# LED_ARRAY.net
KiCad netlist of a schematic drawn in Altium Designer
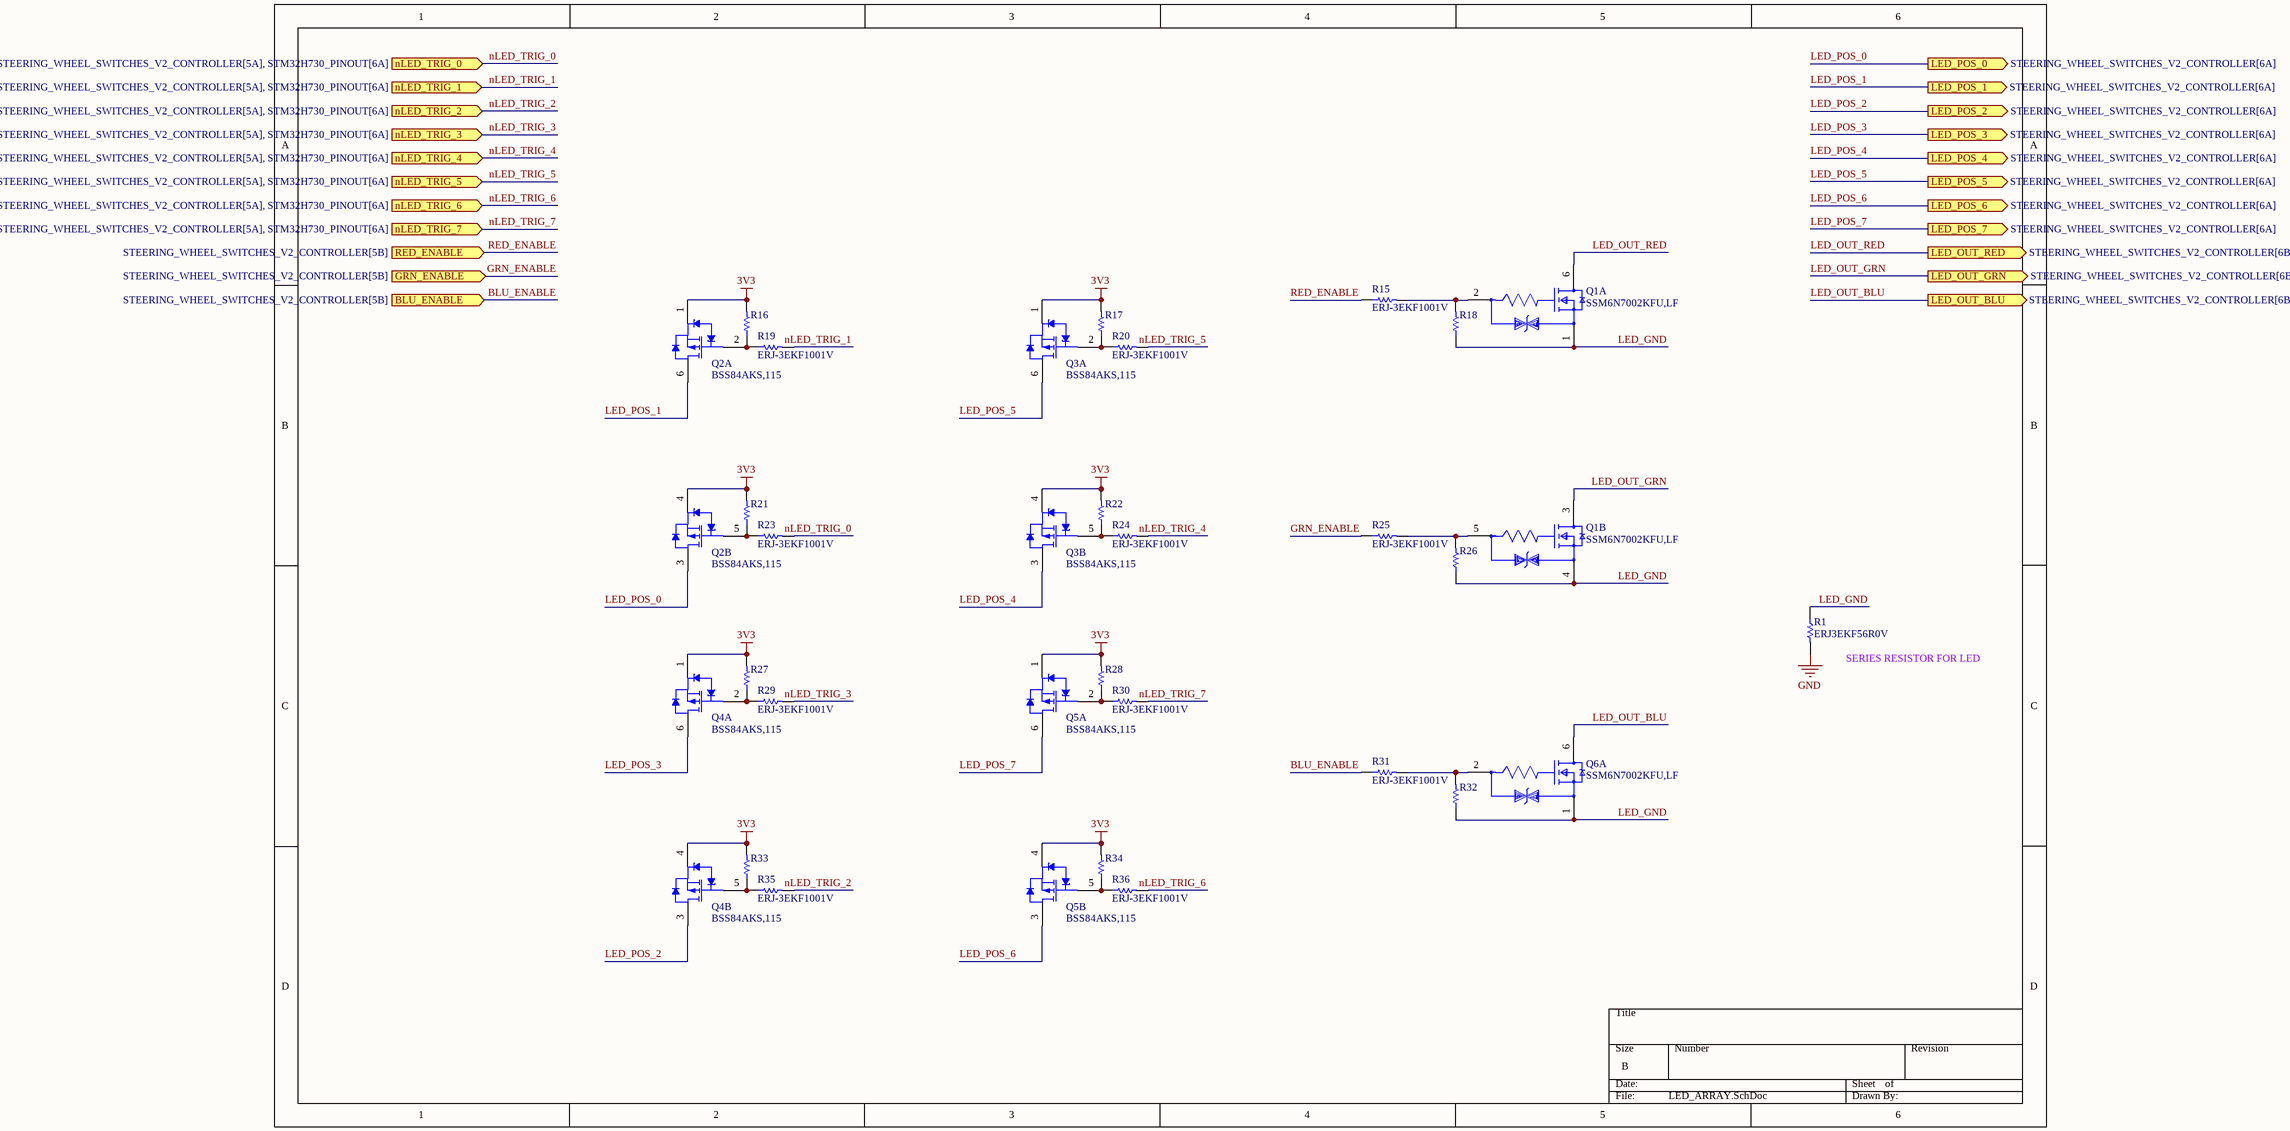
[diagram p0: LED_ARRAY.SchDoc]

(export (version "E")
  (design (tool "Eeschema 10.0.6"))
  (components
    (comp (ref "Q1")
      (value "SSM6N7002KFU,LF")
      (footprint "FP-SSOP6-P-0_65A-MFG")
      (description "MOSFET 2N-CH 60V 0.3A")
      (libsource (lib "Altium Content Vault") (part "088aa6ac103fdeebe0d1c52ece6b7b9"))
    )
    (comp (ref "Q2")
      (value "BSS84AKS,115")
      (footprint "NXP-SOT363_L")
      (description "Dual P-Channel Trench MOSFET, -50 V, -0.16 A, -55 to 150 degC, 6-Pin SOT363, Tape and Reel")
      (fields (field (name "MANUFACTURER") "NXP Semiconductors"))
      (libsource (lib "Altium Content Vault") (part "NXP-PPMOS-SGDSGD-6_A"))
    )
    (comp (ref "Q3")
      (value "BSS84AKS,115")
      (footprint "NXP-SOT363_L")
      (description "Dual P-Channel Trench MOSFET, -50 V, -0.16 A, -55 to 150 degC, 6-Pin SOT363, Tape and Reel")
      (fields (field (name "MANUFACTURER") "NXP Semiconductors"))
      (libsource (lib "Altium Content Vault") (part "NXP-PPMOS-SGDSGD-6_A"))
    )
    (comp (ref "Q4")
      (value "BSS84AKS,115")
      (footprint "NXP-SOT363_L")
      (description "Dual P-Channel Trench MOSFET, -50 V, -0.16 A, -55 to 150 degC, 6-Pin SOT363, Tape and Reel")
      (fields (field (name "MANUFACTURER") "NXP Semiconductors"))
      (libsource (lib "Altium Content Vault") (part "NXP-PPMOS-SGDSGD-6_A"))
    )
    (comp (ref "Q5")
      (value "BSS84AKS,115")
      (footprint "NXP-SOT363_L")
      (description "Dual P-Channel Trench MOSFET, -50 V, -0.16 A, -55 to 150 degC, 6-Pin SOT363, Tape and Reel")
      (fields (field (name "MANUFACTURER") "NXP Semiconductors"))
      (libsource (lib "Altium Content Vault") (part "NXP-PPMOS-SGDSGD-6_A"))
    )
    (comp (ref "Q6")
      (value "SSM6N7002KFU,LF")
      (footprint "FP-SSOP6-P-0_65A-MFG")
      (description "MOSFET 2N-CH 60V 0.3A")
      (libsource (lib "Altium Content Vault") (part "088aa6ac103fdeebe0d1c52ece6b7b9"))
    )
    (comp (ref "R1")
      (value "ERJ3EKF56R0V")
      (footprint "RESC1608X55X30NL15T15")
      (fields (field (name "MANUFACTURER") "Panasonic"))
      (libsource (lib "Altium Content Vault") (part "RES"))
    )
    (comp (ref "R15")
      (value "ERJ-3EKF1001V")
      (footprint "RESC1608X55X30LL15T15")
      (fields (field (name "MANUFACTURER") "Panasonic"))
      (libsource (lib "Altium Content Vault") (part "RES"))
    )
    (comp (ref "R16")
      (value "ERJ3EKF1002V")
      (footprint "RESC1609X55X30LL15T15")
      (description "Chip Resistor, 10 KOhm, +/- 1%, 0.1 W, -55 to 155 degC, 0603 (1608 Metric), RoHS, Tape and Reel")
      (fields (field (name "TOLERANCE") "1%") (field (name "MANUFACTURER") "Panasonic"))
      (libsource (lib "Altium Content Vault") (part "RES-2"))
    )
    (comp (ref "R17")
      (value "ERJ3EKF1002V")
      (footprint "RESC1609X55X30LL15T15")
      (description "Chip Resistor, 10 KOhm, +/- 1%, 0.1 W, -55 to 155 degC, 0603 (1608 Metric), RoHS, Tape and Reel")
      (fields (field (name "TOLERANCE") "1%") (field (name "MANUFACTURER") "Panasonic"))
      (libsource (lib "Altium Content Vault") (part "RES-2"))
    )
    (comp (ref "R18")
      (value "ERJ3EKF1002V")
      (footprint "RESC1609X55X30LL15T15")
      (description "Chip Resistor, 10 KOhm, +/- 1%, 0.1 W, -55 to 155 degC, 0603 (1608 Metric), RoHS, Tape and Reel")
      (fields (field (name "TOLERANCE") "1%") (field (name "MANUFACTURER") "Panasonic"))
      (libsource (lib "Altium Content Vault") (part "RES-2"))
    )
    (comp (ref "R19")
      (value "ERJ-3EKF1001V")
      (footprint "RESC1608X55X30LL15T15")
      (fields (field (name "MANUFACTURER") "Panasonic"))
      (libsource (lib "Altium Content Vault") (part "RES"))
    )
    (comp (ref "R20")
      (value "ERJ-3EKF1001V")
      (footprint "RESC1608X55X30LL15T15")
      (fields (field (name "MANUFACTURER") "Panasonic"))
      (libsource (lib "Altium Content Vault") (part "RES"))
    )
    (comp (ref "R21")
      (value "ERJ3EKF1002V")
      (footprint "RESC1609X55X30LL15T15")
      (description "Chip Resistor, 10 KOhm, +/- 1%, 0.1 W, -55 to 155 degC, 0603 (1608 Metric), RoHS, Tape and Reel")
      (fields (field (name "TOLERANCE") "1%") (field (name "MANUFACTURER") "Panasonic"))
      (libsource (lib "Altium Content Vault") (part "RES-2"))
    )
    (comp (ref "R22")
      (value "ERJ3EKF1002V")
      (footprint "RESC1609X55X30LL15T15")
      (description "Chip Resistor, 10 KOhm, +/- 1%, 0.1 W, -55 to 155 degC, 0603 (1608 Metric), RoHS, Tape and Reel")
      (fields (field (name "TOLERANCE") "1%") (field (name "MANUFACTURER") "Panasonic"))
      (libsource (lib "Altium Content Vault") (part "RES-2"))
    )
    (comp (ref "R23")
      (value "ERJ-3EKF1001V")
      (footprint "RESC1608X55X30LL15T15")
      (fields (field (name "MANUFACTURER") "Panasonic"))
      (libsource (lib "Altium Content Vault") (part "RES"))
    )
    (comp (ref "R24")
      (value "ERJ-3EKF1001V")
      (footprint "RESC1608X55X30LL15T15")
      (fields (field (name "MANUFACTURER") "Panasonic"))
      (libsource (lib "Altium Content Vault") (part "RES"))
    )
    (comp (ref "R25")
      (value "ERJ-3EKF1001V")
      (footprint "RESC1608X55X30LL15T15")
      (fields (field (name "MANUFACTURER") "Panasonic"))
      (libsource (lib "Altium Content Vault") (part "RES"))
    )
    (comp (ref "R26")
      (value "ERJ3EKF1002V")
      (footprint "RESC1609X55X30LL15T15")
      (description "Chip Resistor, 10 KOhm, +/- 1%, 0.1 W, -55 to 155 degC, 0603 (1608 Metric), RoHS, Tape and Reel")
      (fields (field (name "TOLERANCE") "1%") (field (name "MANUFACTURER") "Panasonic"))
      (libsource (lib "Altium Content Vault") (part "RES-2"))
    )
    (comp (ref "R27")
      (value "ERJ3EKF1002V")
      (footprint "RESC1609X55X30LL15T15")
      (description "Chip Resistor, 10 KOhm, +/- 1%, 0.1 W, -55 to 155 degC, 0603 (1608 Metric), RoHS, Tape and Reel")
      (fields (field (name "TOLERANCE") "1%") (field (name "MANUFACTURER") "Panasonic"))
      (libsource (lib "Altium Content Vault") (part "RES-2"))
    )
    (comp (ref "R28")
      (value "ERJ3EKF1002V")
      (footprint "RESC1609X55X30LL15T15")
      (description "Chip Resistor, 10 KOhm, +/- 1%, 0.1 W, -55 to 155 degC, 0603 (1608 Metric), RoHS, Tape and Reel")
      (fields (field (name "TOLERANCE") "1%") (field (name "MANUFACTURER") "Panasonic"))
      (libsource (lib "Altium Content Vault") (part "RES-2"))
    )
    (comp (ref "R29")
      (value "ERJ-3EKF1001V")
      (footprint "RESC1608X55X30LL15T15")
      (fields (field (name "MANUFACTURER") "Panasonic"))
      (libsource (lib "Altium Content Vault") (part "RES"))
    )
    (comp (ref "R30")
      (value "ERJ-3EKF1001V")
      (footprint "RESC1608X55X30LL15T15")
      (fields (field (name "MANUFACTURER") "Panasonic"))
      (libsource (lib "Altium Content Vault") (part "RES"))
    )
    (comp (ref "R31")
      (value "ERJ-3EKF1001V")
      (footprint "RESC1608X55X30LL15T15")
      (fields (field (name "MANUFACTURER") "Panasonic"))
      (libsource (lib "Altium Content Vault") (part "RES"))
    )
    (comp (ref "R32")
      (value "ERJ3EKF1002V")
      (footprint "RESC1609X55X30LL15T15")
      (description "Chip Resistor, 10 KOhm, +/- 1%, 0.1 W, -55 to 155 degC, 0603 (1608 Metric), RoHS, Tape and Reel")
      (fields (field (name "TOLERANCE") "1%") (field (name "MANUFACTURER") "Panasonic"))
      (libsource (lib "Altium Content Vault") (part "RES-2"))
    )
    (comp (ref "R33")
      (value "ERJ3EKF1002V")
      (footprint "RESC1609X55X30LL15T15")
      (description "Chip Resistor, 10 KOhm, +/- 1%, 0.1 W, -55 to 155 degC, 0603 (1608 Metric), RoHS, Tape and Reel")
      (fields (field (name "TOLERANCE") "1%") (field (name "MANUFACTURER") "Panasonic"))
      (libsource (lib "Altium Content Vault") (part "RES-2"))
    )
    (comp (ref "R34")
      (value "ERJ3EKF1002V")
      (footprint "RESC1609X55X30LL15T15")
      (description "Chip Resistor, 10 KOhm, +/- 1%, 0.1 W, -55 to 155 degC, 0603 (1608 Metric), RoHS, Tape and Reel")
      (fields (field (name "TOLERANCE") "1%") (field (name "MANUFACTURER") "Panasonic"))
      (libsource (lib "Altium Content Vault") (part "RES-2"))
    )
    (comp (ref "R35")
      (value "ERJ-3EKF1001V")
      (footprint "RESC1608X55X30LL15T15")
      (fields (field (name "MANUFACTURER") "Panasonic"))
      (libsource (lib "Altium Content Vault") (part "RES"))
    )
    (comp (ref "R36")
      (value "ERJ-3EKF1001V")
      (footprint "RESC1608X55X30LL15T15")
      (fields (field (name "MANUFACTURER") "Panasonic"))
      (libsource (lib "Altium Content Vault") (part "RES"))
    )
  )
  (nets
    (net (code "1") (name "/BLU_ENABLE") (class "Default")
      (node (ref "R31") (pin "1") (pinfunction "1_1") (pintype "passive"))
    )
    (net (code "2") (name "/GRN_ENABLE") (class "Default")
      (node (ref "R25") (pin "1") (pinfunction "1_1") (pintype "passive"))
    )
    (net (code "3") (name "/LED_GND") (class "Default")
      (node (ref "Q1") (pin "1") (pinfunction "Source1_1") (pintype "passive"))
      (node (ref "Q1") (pin "4") (pinfunction "Source2_4") (pintype "passive"))
      (node (ref "Q6") (pin "1") (pinfunction "Source1_1") (pintype "passive"))
      (node (ref "R1") (pin "1") (pinfunction "1_1") (pintype "passive"))
      (node (ref "R18") (pin "1") (pinfunction "1_1") (pintype "passive"))
      (node (ref "R26") (pin "1") (pinfunction "1_1") (pintype "passive"))
      (node (ref "R32") (pin "1") (pinfunction "1_1") (pintype "passive"))
    )
    (net (code "4") (name "/LED_OUT_BLU") (class "Default")
      (node (ref "Q6") (pin "6") (pinfunction "Drain1_6") (pintype "passive"))
    )
    (net (code "5") (name "/LED_OUT_GRN") (class "Default")
      (node (ref "Q1") (pin "3") (pinfunction "Drain2_3") (pintype "passive"))
    )
    (net (code "6") (name "/LED_OUT_RED") (class "Default")
      (node (ref "Q1") (pin "6") (pinfunction "Drain1_6") (pintype "passive"))
    )
    (net (code "7") (name "/LED_POS_0") (class "Default")
      (node (ref "Q2") (pin "3") (pinfunction "D2_3") (pintype "passive"))
    )
    (net (code "8") (name "/LED_POS_1") (class "Default")
      (node (ref "Q2") (pin "6") (pinfunction "D1_6") (pintype "passive"))
    )
    (net (code "9") (name "/LED_POS_2") (class "Default")
      (node (ref "Q4") (pin "3") (pinfunction "D2_3") (pintype "passive"))
    )
    (net (code "10") (name "/LED_POS_3") (class "Default")
      (node (ref "Q4") (pin "6") (pinfunction "D1_6") (pintype "passive"))
    )
    (net (code "11") (name "/LED_POS_4") (class "Default")
      (node (ref "Q3") (pin "3") (pinfunction "D2_3") (pintype "passive"))
    )
    (net (code "12") (name "/LED_POS_5") (class "Default")
      (node (ref "Q3") (pin "6") (pinfunction "D1_6") (pintype "passive"))
    )
    (net (code "13") (name "/LED_POS_6") (class "Default")
      (node (ref "Q5") (pin "3") (pinfunction "D2_3") (pintype "passive"))
    )
    (net (code "14") (name "/LED_POS_7") (class "Default")
      (node (ref "Q5") (pin "6") (pinfunction "D1_6") (pintype "passive"))
    )
    (net (code "15") (name "/RED_ENABLE") (class "Default")
      (node (ref "R15") (pin "1") (pinfunction "1_1") (pintype "passive"))
    )
    (net (code "16") (name "/nLED_TRIG_0") (class "Default")
      (node (ref "R23") (pin "2") (pinfunction "2_2") (pintype "passive"))
    )
    (net (code "17") (name "/nLED_TRIG_1") (class "Default")
      (node (ref "R19") (pin "2") (pinfunction "2_2") (pintype "passive"))
    )
    (net (code "18") (name "/nLED_TRIG_2") (class "Default")
      (node (ref "R35") (pin "2") (pinfunction "2_2") (pintype "passive"))
    )
    (net (code "19") (name "/nLED_TRIG_3") (class "Default")
      (node (ref "R29") (pin "2") (pinfunction "2_2") (pintype "passive"))
    )
    (net (code "20") (name "/nLED_TRIG_4") (class "Default")
      (node (ref "R24") (pin "2") (pinfunction "2_2") (pintype "passive"))
    )
    (net (code "21") (name "/nLED_TRIG_5") (class "Default")
      (node (ref "R20") (pin "2") (pinfunction "2_2") (pintype "passive"))
    )
    (net (code "22") (name "/nLED_TRIG_6") (class "Default")
      (node (ref "R36") (pin "2") (pinfunction "2_2") (pintype "passive"))
    )
    (net (code "23") (name "/nLED_TRIG_7") (class "Default")
      (node (ref "R30") (pin "2") (pinfunction "2_2") (pintype "passive"))
    )
    (net (code "24") (name "3V3") (class "Default")
      (node (ref "Q2") (pin "1") (pinfunction "S1_1") (pintype "passive"))
      (node (ref "Q2") (pin "4") (pinfunction "S2_4") (pintype "passive"))
      (node (ref "Q3") (pin "1") (pinfunction "S1_1") (pintype "passive"))
      (node (ref "Q3") (pin "4") (pinfunction "S2_4") (pintype "passive"))
      (node (ref "Q4") (pin "1") (pinfunction "S1_1") (pintype "passive"))
      (node (ref "Q4") (pin "4") (pinfunction "S2_4") (pintype "passive"))
      (node (ref "Q5") (pin "1") (pinfunction "S1_1") (pintype "passive"))
      (node (ref "Q5") (pin "4") (pinfunction "S2_4") (pintype "passive"))
      (node (ref "R16") (pin "2") (pinfunction "2_2") (pintype "passive"))
      (node (ref "R17") (pin "2") (pinfunction "2_2") (pintype "passive"))
      (node (ref "R21") (pin "2") (pinfunction "2_2") (pintype "passive"))
      (node (ref "R22") (pin "2") (pinfunction "2_2") (pintype "passive"))
      (node (ref "R27") (pin "2") (pinfunction "2_2") (pintype "passive"))
      (node (ref "R28") (pin "2") (pinfunction "2_2") (pintype "passive"))
      (node (ref "R33") (pin "2") (pinfunction "2_2") (pintype "passive"))
      (node (ref "R34") (pin "2") (pinfunction "2_2") (pintype "passive"))
    )
    (net (code "25") (name "GND") (class "Default")
      (node (ref "R1") (pin "2") (pinfunction "2_2") (pintype "passive"))
    )
    (net (code "26") (name "Net-(Q1A-Gate1)") (class "Default")
      (node (ref "Q1") (pin "2") (pinfunction "Gate1_2") (pintype "passive"))
      (node (ref "R15") (pin "2") (pinfunction "2_2") (pintype "passive"))
      (node (ref "R18") (pin "2") (pinfunction "2_2") (pintype "passive"))
    )
    (net (code "27") (name "Net-(Q1B-Gate2)") (class "Default")
      (node (ref "Q1") (pin "5") (pinfunction "Gate2_5") (pintype "passive"))
      (node (ref "R25") (pin "2") (pinfunction "2_2") (pintype "passive"))
      (node (ref "R26") (pin "2") (pinfunction "2_2") (pintype "passive"))
    )
    (net (code "28") (name "Net-(Q2A-G1)") (class "Default")
      (node (ref "Q2") (pin "2") (pinfunction "G1_2") (pintype "passive"))
      (node (ref "R16") (pin "1") (pinfunction "1_1") (pintype "passive"))
      (node (ref "R19") (pin "1") (pinfunction "1_1") (pintype "passive"))
    )
    (net (code "29") (name "Net-(Q2B-G2)") (class "Default")
      (node (ref "Q2") (pin "5") (pinfunction "G2_5") (pintype "passive"))
      (node (ref "R21") (pin "1") (pinfunction "1_1") (pintype "passive"))
      (node (ref "R23") (pin "1") (pinfunction "1_1") (pintype "passive"))
    )
    (net (code "30") (name "Net-(Q3A-G1)") (class "Default")
      (node (ref "Q3") (pin "2") (pinfunction "G1_2") (pintype "passive"))
      (node (ref "R17") (pin "1") (pinfunction "1_1") (pintype "passive"))
      (node (ref "R20") (pin "1") (pinfunction "1_1") (pintype "passive"))
    )
    (net (code "31") (name "Net-(Q3B-G2)") (class "Default")
      (node (ref "Q3") (pin "5") (pinfunction "G2_5") (pintype "passive"))
      (node (ref "R22") (pin "1") (pinfunction "1_1") (pintype "passive"))
      (node (ref "R24") (pin "1") (pinfunction "1_1") (pintype "passive"))
    )
    (net (code "32") (name "Net-(Q4A-G1)") (class "Default")
      (node (ref "Q4") (pin "2") (pinfunction "G1_2") (pintype "passive"))
      (node (ref "R27") (pin "1") (pinfunction "1_1") (pintype "passive"))
      (node (ref "R29") (pin "1") (pinfunction "1_1") (pintype "passive"))
    )
    (net (code "33") (name "Net-(Q4B-G2)") (class "Default")
      (node (ref "Q4") (pin "5") (pinfunction "G2_5") (pintype "passive"))
      (node (ref "R33") (pin "1") (pinfunction "1_1") (pintype "passive"))
      (node (ref "R35") (pin "1") (pinfunction "1_1") (pintype "passive"))
    )
    (net (code "34") (name "Net-(Q5A-G1)") (class "Default")
      (node (ref "Q5") (pin "2") (pinfunction "G1_2") (pintype "passive"))
      (node (ref "R28") (pin "1") (pinfunction "1_1") (pintype "passive"))
      (node (ref "R30") (pin "1") (pinfunction "1_1") (pintype "passive"))
    )
    (net (code "35") (name "Net-(Q5B-G2)") (class "Default")
      (node (ref "Q5") (pin "5") (pinfunction "G2_5") (pintype "passive"))
      (node (ref "R34") (pin "1") (pinfunction "1_1") (pintype "passive"))
      (node (ref "R36") (pin "1") (pinfunction "1_1") (pintype "passive"))
    )
    (net (code "36") (name "Net-(Q6A-Gate1)") (class "Default")
      (node (ref "Q6") (pin "2") (pinfunction "Gate1_2") (pintype "passive"))
      (node (ref "R31") (pin "2") (pinfunction "2_2") (pintype "passive"))
      (node (ref "R32") (pin "2") (pinfunction "2_2") (pintype "passive"))
    )
  )
)
